# SCHEMAT_WY_WIETLACZA.net
KiCad netlist of a schematic drawn in EAGLE
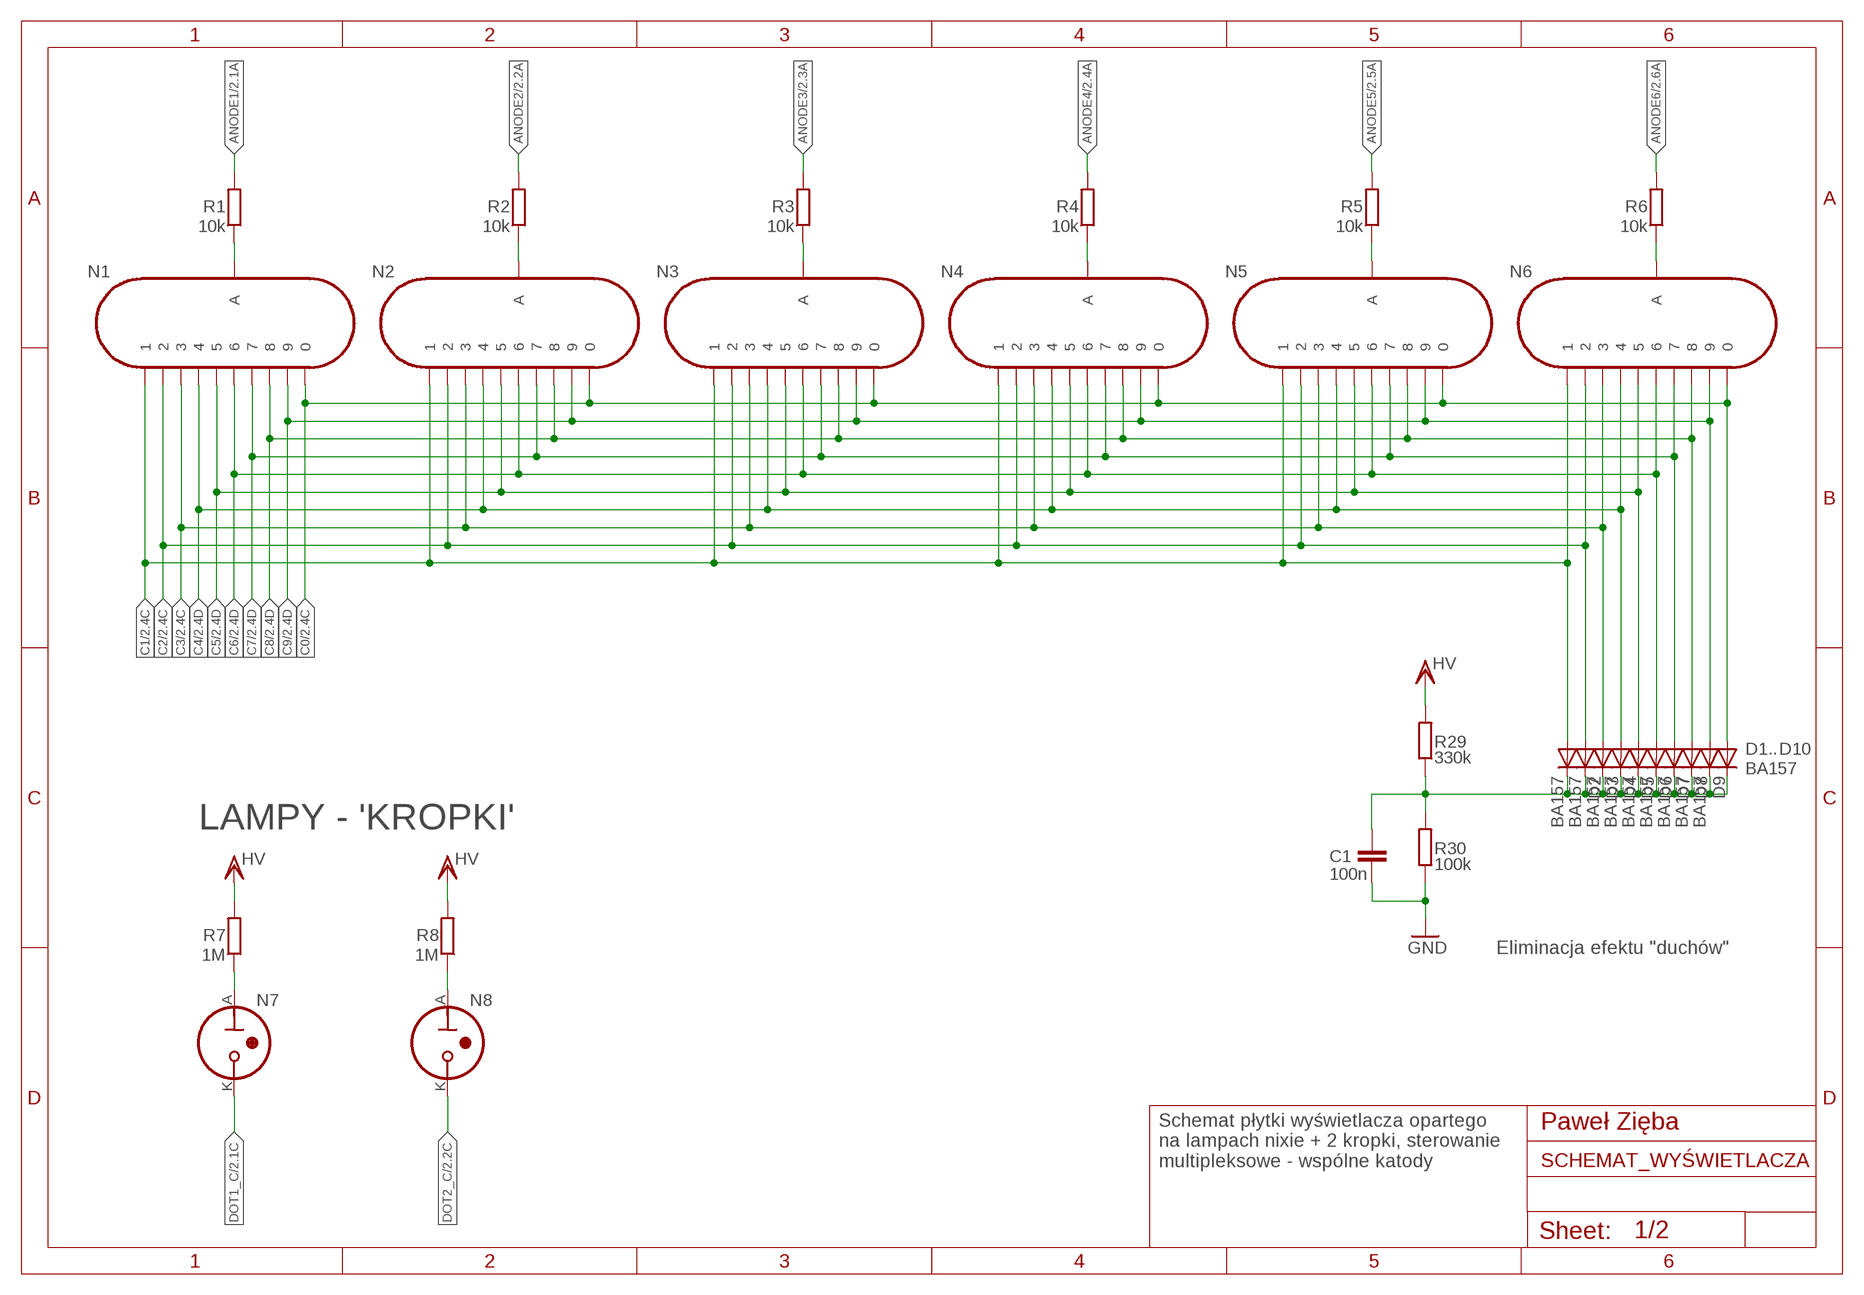
[diagram p0: schematic, sheet 1]
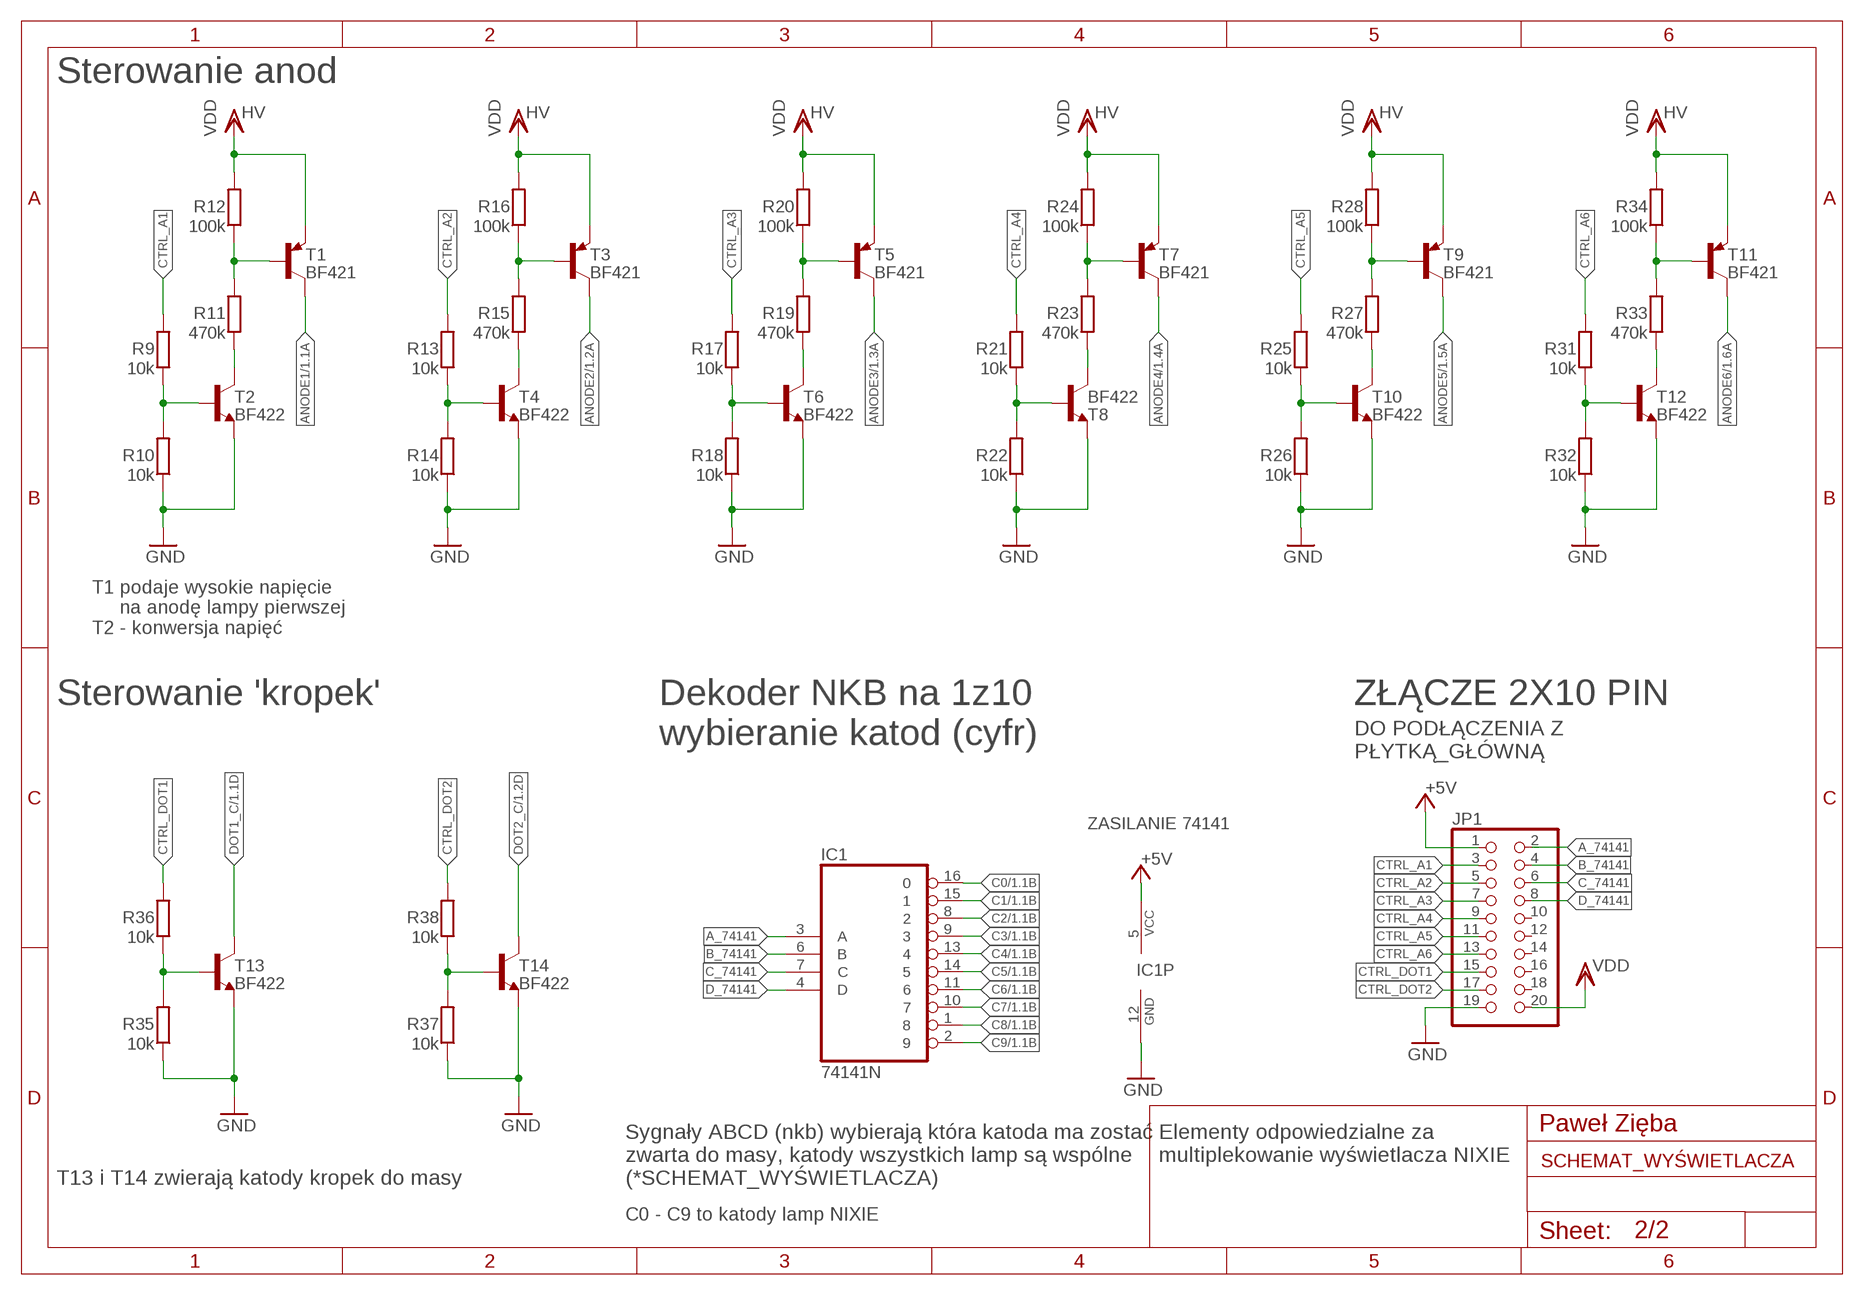
[diagram p1: schematic, sheet 2]

(export (version "E")
  (design (tool "Eeschema 10.0.6"))
  (components
    (comp (ref "IC1")
      (value "74141N")
      (footprint "eagle-import:DIL16")
      (libsource (lib "eagle-import") (part "74141N"))
    )
    (comp (ref "JP1")
      (value "PINHD-2X10")
      (footprint "eagle-import:2X10")
      (libsource (lib "eagle-import") (part "PINHD-2X10"))
    )
    (comp (ref "R9")
      (value "10k")
      (footprint "eagle-import:204_7")
      (libsource (lib "eagle-import") (part "R-EU7"))
    )
    (comp (ref "R10")
      (value "10k")
      (footprint "eagle-import:204_7")
      (libsource (lib "eagle-import") (part "R-EU7"))
    )
    (comp (ref "R11")
      (value "470k")
      (footprint "eagle-import:204_7")
      (libsource (lib "eagle-import") (part "R-EU7"))
    )
    (comp (ref "R12")
      (value "100k")
      (footprint "eagle-import:204_7")
      (libsource (lib "eagle-import") (part "R-EU7"))
    )
    (comp (ref "R13")
      (value "10k")
      (footprint "eagle-import:204_7")
      (libsource (lib "eagle-import") (part "R-EU7"))
    )
    (comp (ref "R14")
      (value "10k")
      (footprint "eagle-import:204_7")
      (libsource (lib "eagle-import") (part "R-EU7"))
    )
    (comp (ref "R15")
      (value "470k")
      (footprint "eagle-import:204_7")
      (libsource (lib "eagle-import") (part "R-EU7"))
    )
    (comp (ref "R16")
      (value "100k")
      (footprint "eagle-import:204_7")
      (libsource (lib "eagle-import") (part "R-EU7"))
    )
    (comp (ref "R17")
      (value "10k")
      (footprint "eagle-import:204_7")
      (libsource (lib "eagle-import") (part "R-EU7"))
    )
    (comp (ref "R18")
      (value "10k")
      (footprint "eagle-import:204_7")
      (libsource (lib "eagle-import") (part "R-EU7"))
    )
    (comp (ref "R19")
      (value "470k")
      (footprint "eagle-import:204_7")
      (libsource (lib "eagle-import") (part "R-EU7"))
    )
    (comp (ref "R20")
      (value "100k")
      (footprint "eagle-import:204_7")
      (libsource (lib "eagle-import") (part "R-EU7"))
    )
    (comp (ref "R21")
      (value "10k")
      (footprint "eagle-import:204_7")
      (libsource (lib "eagle-import") (part "R-EU7"))
    )
    (comp (ref "R22")
      (value "10k")
      (footprint "eagle-import:204_7")
      (libsource (lib "eagle-import") (part "R-EU7"))
    )
    (comp (ref "R23")
      (value "470k")
      (footprint "eagle-import:204_7")
      (libsource (lib "eagle-import") (part "R-EU7"))
    )
    (comp (ref "R24")
      (value "100k")
      (footprint "eagle-import:204_7")
      (libsource (lib "eagle-import") (part "R-EU7"))
    )
    (comp (ref "R25")
      (value "10k")
      (footprint "eagle-import:204_7")
      (libsource (lib "eagle-import") (part "R-EU7"))
    )
    (comp (ref "R26")
      (value "10k")
      (footprint "eagle-import:204_7")
      (libsource (lib "eagle-import") (part "R-EU7"))
    )
    (comp (ref "R27")
      (value "470k")
      (footprint "eagle-import:204_7")
      (libsource (lib "eagle-import") (part "R-EU7"))
    )
    (comp (ref "R28")
      (value "100k")
      (footprint "eagle-import:204_7")
      (libsource (lib "eagle-import") (part "R-EU7"))
    )
    (comp (ref "R31")
      (value "10k")
      (footprint "eagle-import:204_7")
      (libsource (lib "eagle-import") (part "R-EU7"))
    )
    (comp (ref "R32")
      (value "10k")
      (footprint "eagle-import:204_7")
      (libsource (lib "eagle-import") (part "R-EU7"))
    )
    (comp (ref "R33")
      (value "470k")
      (footprint "eagle-import:204_7")
      (libsource (lib "eagle-import") (part "R-EU7"))
    )
    (comp (ref "R34")
      (value "100k")
      (footprint "eagle-import:204_7")
      (libsource (lib "eagle-import") (part "R-EU7"))
    )
    (comp (ref "R35")
      (value "10k")
      (footprint "eagle-import:204_7")
      (libsource (lib "eagle-import") (part "R-EU7"))
    )
    (comp (ref "R36")
      (value "10k")
      (footprint "eagle-import:204_7")
      (libsource (lib "eagle-import") (part "R-EU7"))
    )
    (comp (ref "R37")
      (value "10k")
      (footprint "eagle-import:204_7")
      (libsource (lib "eagle-import") (part "R-EU7"))
    )
    (comp (ref "R38")
      (value "10k")
      (footprint "eagle-import:204_7")
      (libsource (lib "eagle-import") (part "R-EU7"))
    )
    (comp (ref "T1")
      (value "BF421")
      (footprint "eagle-import:TO92-BCE")
      (libsource (lib "eagle-import") (part "BF421"))
    )
    (comp (ref "T2")
      (value "BF422")
      (footprint "eagle-import:TO92-BCE")
      (libsource (lib "eagle-import") (part "-NPN-TO92-BCEBF422"))
    )
    (comp (ref "T3")
      (value "BF421")
      (footprint "eagle-import:TO92-BCE")
      (libsource (lib "eagle-import") (part "BF421"))
    )
    (comp (ref "T4")
      (value "BF422")
      (footprint "eagle-import:TO92-BCE")
      (libsource (lib "eagle-import") (part "-NPN-TO92-BCEBF422"))
    )
    (comp (ref "T5")
      (value "BF421")
      (footprint "eagle-import:TO92-BCE")
      (libsource (lib "eagle-import") (part "BF421"))
    )
    (comp (ref "T6")
      (value "BF422")
      (footprint "eagle-import:TO92-BCE")
      (libsource (lib "eagle-import") (part "-NPN-TO92-BCEBF422"))
    )
    (comp (ref "T7")
      (value "BF421")
      (footprint "eagle-import:TO92-BCE")
      (libsource (lib "eagle-import") (part "BF421"))
    )
    (comp (ref "T8")
      (value "BF422")
      (footprint "eagle-import:TO92-BCE")
      (libsource (lib "eagle-import") (part "-NPN-TO92-BCEBF422"))
    )
    (comp (ref "T9")
      (value "BF421")
      (footprint "eagle-import:TO92-BCE")
      (libsource (lib "eagle-import") (part "BF421"))
    )
    (comp (ref "T10")
      (value "BF422")
      (footprint "eagle-import:TO92-BCE")
      (libsource (lib "eagle-import") (part "-NPN-TO92-BCEBF422"))
    )
    (comp (ref "T11")
      (value "BF421")
      (footprint "eagle-import:TO92-BCE")
      (libsource (lib "eagle-import") (part "BF421"))
    )
    (comp (ref "T12")
      (value "BF422")
      (footprint "eagle-import:TO92-BCE")
      (libsource (lib "eagle-import") (part "-NPN-TO92-BCEBF422"))
    )
    (comp (ref "T13")
      (value "BF422")
      (footprint "eagle-import:TO92-BCE")
      (libsource (lib "eagle-import") (part "-NPN-TO92-BCEBF422"))
    )
    (comp (ref "T14")
      (value "BF422")
      (footprint "eagle-import:TO92-BCE")
      (libsource (lib "eagle-import") (part "-NPN-TO92-BCEBF422"))
    )
    (comp (ref "C1")
      (value "100n")
      (footprint "eagle-import:C50-45-75")
      (libsource (lib "eagle-import") (part "C-EU050-045-075"))
    )
    (comp (ref "D1")
      (value "BA157")
      (footprint "eagle-import:P1-10")
      (libsource (lib "eagle-import") (part "BA157"))
    )
    (comp (ref "D2")
      (value "BA157")
      (footprint "eagle-import:P1-10")
      (libsource (lib "eagle-import") (part "BA157"))
    )
    (comp (ref "D3")
      (value "BA157")
      (footprint "eagle-import:P1-10")
      (libsource (lib "eagle-import") (part "BA157"))
    )
    (comp (ref "D4")
      (value "BA157")
      (footprint "eagle-import:P1-10")
      (libsource (lib "eagle-import") (part "BA157"))
    )
    (comp (ref "D5")
      (value "BA157")
      (footprint "eagle-import:P1-10")
      (libsource (lib "eagle-import") (part "BA157"))
    )
    (comp (ref "D6")
      (value "BA157")
      (footprint "eagle-import:P1-10")
      (libsource (lib "eagle-import") (part "BA157"))
    )
    (comp (ref "D7")
      (value "BA157")
      (footprint "eagle-import:P1-10")
      (libsource (lib "eagle-import") (part "BA157"))
    )
    (comp (ref "D8")
      (value "BA157")
      (footprint "eagle-import:P1-10")
      (libsource (lib "eagle-import") (part "BA157"))
    )
    (comp (ref "D9")
      (value "BA157")
      (footprint "eagle-import:P1-10")
      (libsource (lib "eagle-import") (part "BA157"))
    )
    (comp (ref "D10")
      (value "BA157")
      (footprint "eagle-import:P1-10")
      (libsource (lib "eagle-import") (part "BA157"))
    )
    (comp (ref "N1")
      (value "IN-8")
      (footprint "eagle-import:IN-8")
      (libsource (lib "eagle-import") (part "IN-8"))
    )
    (comp (ref "N2")
      (value "IN-8")
      (footprint "eagle-import:IN-8")
      (libsource (lib "eagle-import") (part "IN-8"))
    )
    (comp (ref "N3")
      (value "IN-8")
      (footprint "eagle-import:IN-8")
      (libsource (lib "eagle-import") (part "IN-8"))
    )
    (comp (ref "N4")
      (value "IN-8")
      (footprint "eagle-import:IN-8")
      (libsource (lib "eagle-import") (part "IN-8"))
    )
    (comp (ref "N5")
      (value "IN-8")
      (footprint "eagle-import:IN-8")
      (libsource (lib "eagle-import") (part "IN-8"))
    )
    (comp (ref "N6")
      (value "IN-8")
      (footprint "eagle-import:IN-8")
      (libsource (lib "eagle-import") (part "IN-8"))
    )
    (comp (ref "N7")
      (value "IN-3")
      (footprint "eagle-import:IN-3")
      (libsource (lib "eagle-import") (part "IN-3"))
    )
    (comp (ref "N8")
      (value "IN-3")
      (footprint "eagle-import:IN-3")
      (libsource (lib "eagle-import") (part "IN-3"))
    )
    (comp (ref "R1")
      (value "10k")
      (footprint "eagle-import:204_7")
      (libsource (lib "eagle-import") (part "R-EU7"))
    )
    (comp (ref "R2")
      (value "10k")
      (footprint "eagle-import:204_7")
      (libsource (lib "eagle-import") (part "R-EU7"))
    )
    (comp (ref "R3")
      (value "10k")
      (footprint "eagle-import:204_7")
      (libsource (lib "eagle-import") (part "R-EU7"))
    )
    (comp (ref "R4")
      (value "10k")
      (footprint "eagle-import:204_7")
      (libsource (lib "eagle-import") (part "R-EU7"))
    )
    (comp (ref "R5")
      (value "10k")
      (footprint "eagle-import:204_7")
      (libsource (lib "eagle-import") (part "R-EU7"))
    )
    (comp (ref "R6")
      (value "10k")
      (footprint "eagle-import:204_7")
      (libsource (lib "eagle-import") (part "R-EU7"))
    )
    (comp (ref "R7")
      (value "1M")
      (footprint "eagle-import:204_7")
      (libsource (lib "eagle-import") (part "R-EU7"))
    )
    (comp (ref "R8")
      (value "1M")
      (footprint "eagle-import:204_7")
      (libsource (lib "eagle-import") (part "R-EU7"))
    )
    (comp (ref "R29")
      (value "330k")
      (footprint "eagle-import:204_7")
      (libsource (lib "eagle-import") (part "R-EU7"))
    )
    (comp (ref "R30")
      (value "100k")
      (footprint "eagle-import:204_7")
      (libsource (lib "eagle-import") (part "R-EU7"))
    )
  )
  (nets
    (net (code "1") (name "+5V") (class "Default")
      (node (ref "IC1") (pin "5") (pinfunction "VCC_5") (pintype "power_in"))
      (node (ref "JP1") (pin "1") (pinfunction "1_1") (pintype "passive"))
    )
    (net (code "2") (name "ANODE1") (class "Default")
      (node (ref "R1") (pin "P$2") (pinfunction "2_P$2") (pintype "passive"))
      (node (ref "T1") (pin "C") (pinfunction "C_C") (pintype "passive"))
    )
    (net (code "3") (name "ANODE2") (class "Default")
      (node (ref "R2") (pin "P$2") (pinfunction "2_P$2") (pintype "passive"))
      (node (ref "T3") (pin "C") (pinfunction "C_C") (pintype "passive"))
    )
    (net (code "4") (name "ANODE3") (class "Default")
      (node (ref "R3") (pin "P$2") (pinfunction "2_P$2") (pintype "passive"))
      (node (ref "T5") (pin "C") (pinfunction "C_C") (pintype "passive"))
    )
    (net (code "5") (name "ANODE4") (class "Default")
      (node (ref "R4") (pin "P$2") (pinfunction "2_P$2") (pintype "passive"))
      (node (ref "T7") (pin "C") (pinfunction "C_C") (pintype "passive"))
    )
    (net (code "6") (name "ANODE5") (class "Default")
      (node (ref "R5") (pin "P$2") (pinfunction "2_P$2") (pintype "passive"))
      (node (ref "T9") (pin "C") (pinfunction "C_C") (pintype "passive"))
    )
    (net (code "7") (name "ANODE6") (class "Default")
      (node (ref "R6") (pin "P$2") (pinfunction "2_P$2") (pintype "passive"))
      (node (ref "T11") (pin "C") (pinfunction "C_C") (pintype "passive"))
    )
    (net (code "8") (name "A_74141") (class "Default")
      (node (ref "IC1") (pin "3") (pinfunction "A_3") (pintype "input"))
      (node (ref "JP1") (pin "2") (pinfunction "2_2") (pintype "passive"))
    )
    (net (code "9") (name "B_74141") (class "Default")
      (node (ref "IC1") (pin "6") (pinfunction "B_6") (pintype "input"))
      (node (ref "JP1") (pin "4") (pinfunction "4_4") (pintype "passive"))
    )
    (net (code "10") (name "C0") (class "Default")
      (node (ref "D10") (pin "A") (pinfunction "A_A") (pintype "passive"))
      (node (ref "IC1") (pin "16") (pinfunction "0_16") (pintype "open_collector"))
      (node (ref "N1") (pin "0") (pinfunction "0_0") (pintype "bidirectional"))
      (node (ref "N2") (pin "0") (pinfunction "0_0") (pintype "bidirectional"))
      (node (ref "N3") (pin "0") (pinfunction "0_0") (pintype "bidirectional"))
      (node (ref "N4") (pin "0") (pinfunction "0_0") (pintype "bidirectional"))
      (node (ref "N5") (pin "0") (pinfunction "0_0") (pintype "bidirectional"))
      (node (ref "N6") (pin "0") (pinfunction "0_0") (pintype "bidirectional"))
    )
    (net (code "11") (name "C1") (class "Default")
      (node (ref "D1") (pin "A") (pinfunction "A_A") (pintype "passive"))
      (node (ref "IC1") (pin "15") (pinfunction "1_15") (pintype "open_collector"))
      (node (ref "N1") (pin "1") (pinfunction "1_1") (pintype "bidirectional"))
      (node (ref "N2") (pin "1") (pinfunction "1_1") (pintype "bidirectional"))
      (node (ref "N3") (pin "1") (pinfunction "1_1") (pintype "bidirectional"))
      (node (ref "N4") (pin "1") (pinfunction "1_1") (pintype "bidirectional"))
      (node (ref "N5") (pin "1") (pinfunction "1_1") (pintype "bidirectional"))
      (node (ref "N6") (pin "1") (pinfunction "1_1") (pintype "bidirectional"))
    )
    (net (code "12") (name "C2") (class "Default")
      (node (ref "D2") (pin "A") (pinfunction "A_A") (pintype "passive"))
      (node (ref "IC1") (pin "8") (pinfunction "2_8") (pintype "open_collector"))
      (node (ref "N1") (pin "2") (pinfunction "2_2") (pintype "bidirectional"))
      (node (ref "N2") (pin "2") (pinfunction "2_2") (pintype "bidirectional"))
      (node (ref "N3") (pin "2") (pinfunction "2_2") (pintype "bidirectional"))
      (node (ref "N4") (pin "2") (pinfunction "2_2") (pintype "bidirectional"))
      (node (ref "N5") (pin "2") (pinfunction "2_2") (pintype "bidirectional"))
      (node (ref "N6") (pin "2") (pinfunction "2_2") (pintype "bidirectional"))
    )
    (net (code "13") (name "C3") (class "Default")
      (node (ref "D3") (pin "A") (pinfunction "A_A") (pintype "passive"))
      (node (ref "IC1") (pin "9") (pinfunction "3_9") (pintype "open_collector"))
      (node (ref "N1") (pin "3") (pinfunction "3_3") (pintype "bidirectional"))
      (node (ref "N2") (pin "3") (pinfunction "3_3") (pintype "bidirectional"))
      (node (ref "N3") (pin "3") (pinfunction "3_3") (pintype "bidirectional"))
      (node (ref "N4") (pin "3") (pinfunction "3_3") (pintype "bidirectional"))
      (node (ref "N5") (pin "3") (pinfunction "3_3") (pintype "bidirectional"))
      (node (ref "N6") (pin "3") (pinfunction "3_3") (pintype "bidirectional"))
    )
    (net (code "14") (name "C4") (class "Default")
      (node (ref "D4") (pin "A") (pinfunction "A_A") (pintype "passive"))
      (node (ref "IC1") (pin "13") (pinfunction "4_13") (pintype "open_collector"))
      (node (ref "N1") (pin "4") (pinfunction "4_4") (pintype "bidirectional"))
      (node (ref "N2") (pin "4") (pinfunction "4_4") (pintype "bidirectional"))
      (node (ref "N3") (pin "4") (pinfunction "4_4") (pintype "bidirectional"))
      (node (ref "N4") (pin "4") (pinfunction "4_4") (pintype "bidirectional"))
      (node (ref "N5") (pin "4") (pinfunction "4_4") (pintype "bidirectional"))
      (node (ref "N6") (pin "4") (pinfunction "4_4") (pintype "bidirectional"))
    )
    (net (code "15") (name "C5") (class "Default")
      (node (ref "D5") (pin "A") (pinfunction "A_A") (pintype "passive"))
      (node (ref "IC1") (pin "14") (pinfunction "5_14") (pintype "open_collector"))
      (node (ref "N1") (pin "5") (pinfunction "5_5") (pintype "bidirectional"))
      (node (ref "N2") (pin "5") (pinfunction "5_5") (pintype "bidirectional"))
      (node (ref "N3") (pin "5") (pinfunction "5_5") (pintype "bidirectional"))
      (node (ref "N4") (pin "5") (pinfunction "5_5") (pintype "bidirectional"))
      (node (ref "N5") (pin "5") (pinfunction "5_5") (pintype "bidirectional"))
      (node (ref "N6") (pin "5") (pinfunction "5_5") (pintype "bidirectional"))
    )
    (net (code "16") (name "C6") (class "Default")
      (node (ref "D6") (pin "A") (pinfunction "A_A") (pintype "passive"))
      (node (ref "IC1") (pin "11") (pinfunction "6_11") (pintype "open_collector"))
      (node (ref "N1") (pin "6") (pinfunction "6_6") (pintype "bidirectional"))
      (node (ref "N2") (pin "6") (pinfunction "6_6") (pintype "bidirectional"))
      (node (ref "N3") (pin "6") (pinfunction "6_6") (pintype "bidirectional"))
      (node (ref "N4") (pin "6") (pinfunction "6_6") (pintype "bidirectional"))
      (node (ref "N5") (pin "6") (pinfunction "6_6") (pintype "bidirectional"))
      (node (ref "N6") (pin "6") (pinfunction "6_6") (pintype "bidirectional"))
    )
    (net (code "17") (name "C7") (class "Default")
      (node (ref "D7") (pin "A") (pinfunction "A_A") (pintype "passive"))
      (node (ref "IC1") (pin "10") (pinfunction "7_10") (pintype "open_collector"))
      (node (ref "N1") (pin "7") (pinfunction "7_7") (pintype "bidirectional"))
      (node (ref "N2") (pin "7") (pinfunction "7_7") (pintype "bidirectional"))
      (node (ref "N3") (pin "7") (pinfunction "7_7") (pintype "bidirectional"))
      (node (ref "N4") (pin "7") (pinfunction "7_7") (pintype "bidirectional"))
      (node (ref "N5") (pin "7") (pinfunction "7_7") (pintype "bidirectional"))
      (node (ref "N6") (pin "7") (pinfunction "7_7") (pintype "bidirectional"))
    )
    (net (code "18") (name "C8") (class "Default")
      (node (ref "D8") (pin "A") (pinfunction "A_A") (pintype "passive"))
      (node (ref "IC1") (pin "1") (pinfunction "8_1") (pintype "open_collector"))
      (node (ref "N1") (pin "8") (pinfunction "8_8") (pintype "bidirectional"))
      (node (ref "N2") (pin "8") (pinfunction "8_8") (pintype "bidirectional"))
      (node (ref "N3") (pin "8") (pinfunction "8_8") (pintype "bidirectional"))
      (node (ref "N4") (pin "8") (pinfunction "8_8") (pintype "bidirectional"))
      (node (ref "N5") (pin "8") (pinfunction "8_8") (pintype "bidirectional"))
      (node (ref "N6") (pin "8") (pinfunction "8_8") (pintype "bidirectional"))
    )
    (net (code "19") (name "C9") (class "Default")
      (node (ref "D9") (pin "A") (pinfunction "A_A") (pintype "passive"))
      (node (ref "IC1") (pin "2") (pinfunction "9_2") (pintype "open_collector"))
      (node (ref "N1") (pin "9") (pinfunction "9_9") (pintype "bidirectional"))
      (node (ref "N2") (pin "9") (pinfunction "9_9") (pintype "bidirectional"))
      (node (ref "N3") (pin "9") (pinfunction "9_9") (pintype "bidirectional"))
      (node (ref "N4") (pin "9") (pinfunction "9_9") (pintype "bidirectional"))
      (node (ref "N5") (pin "9") (pinfunction "9_9") (pintype "bidirectional"))
      (node (ref "N6") (pin "9") (pinfunction "9_9") (pintype "bidirectional"))
    )
    (net (code "20") (name "CTRL_A1") (class "Default")
      (node (ref "JP1") (pin "3") (pinfunction "3_3") (pintype "passive"))
      (node (ref "R9") (pin "P$2") (pinfunction "2_P$2") (pintype "passive"))
    )
    (net (code "21") (name "CTRL_A2") (class "Default")
      (node (ref "JP1") (pin "5") (pinfunction "5_5") (pintype "passive"))
      (node (ref "R13") (pin "P$2") (pinfunction "2_P$2") (pintype "passive"))
    )
    (net (code "22") (name "CTRL_A3") (class "Default")
      (node (ref "JP1") (pin "7") (pinfunction "7_7") (pintype "passive"))
      (node (ref "R17") (pin "P$2") (pinfunction "2_P$2") (pintype "passive"))
    )
    (net (code "23") (name "CTRL_A4") (class "Default")
      (node (ref "JP1") (pin "9") (pinfunction "9_9") (pintype "passive"))
      (node (ref "R21") (pin "P$2") (pinfunction "2_P$2") (pintype "passive"))
    )
    (net (code "24") (name "CTRL_A5") (class "Default")
      (node (ref "JP1") (pin "11") (pinfunction "11_11") (pintype "passive"))
      (node (ref "R25") (pin "P$2") (pinfunction "2_P$2") (pintype "passive"))
    )
    (net (code "25") (name "CTRL_A6") (class "Default")
      (node (ref "JP1") (pin "13") (pinfunction "13_13") (pintype "passive"))
      (node (ref "R31") (pin "P$2") (pinfunction "2_P$2") (pintype "passive"))
    )
    (net (code "26") (name "CTRL_DOT1") (class "Default")
      (node (ref "JP1") (pin "15") (pinfunction "15_15") (pintype "passive"))
      (node (ref "R36") (pin "P$2") (pinfunction "2_P$2") (pintype "passive"))
    )
    (net (code "27") (name "CTRL_DOT2") (class "Default")
      (node (ref "JP1") (pin "17") (pinfunction "17_17") (pintype "passive"))
      (node (ref "R38") (pin "P$2") (pinfunction "2_P$2") (pintype "passive"))
    )
    (net (code "28") (name "C_74141") (class "Default")
      (node (ref "IC1") (pin "7") (pinfunction "C_7") (pintype "input"))
      (node (ref "JP1") (pin "6") (pinfunction "6_6") (pintype "passive"))
    )
    (net (code "29") (name "DOT1_C") (class "Default")
      (node (ref "N7") (pin "K") (pinfunction "K_K") (pintype "bidirectional"))
      (node (ref "T13") (pin "C") (pinfunction "C_C") (pintype "passive"))
    )
    (net (code "30") (name "DOT2_C") (class "Default")
      (node (ref "N8") (pin "K") (pinfunction "K_K") (pintype "bidirectional"))
      (node (ref "T14") (pin "C") (pinfunction "C_C") (pintype "passive"))
    )
    (net (code "31") (name "D_74141") (class "Default")
      (node (ref "IC1") (pin "4") (pinfunction "D_4") (pintype "input"))
      (node (ref "JP1") (pin "8") (pinfunction "8_8") (pintype "passive"))
    )
    (net (code "32") (name "GND") (class "Default")
      (node (ref "C1") (pin "P$2") (pinfunction "2_P$2") (pintype "passive"))
      (node (ref "IC1") (pin "12") (pinfunction "GND_12") (pintype "power_in"))
      (node (ref "JP1") (pin "19") (pinfunction "19_19") (pintype "passive"))
      (node (ref "R10") (pin "P$1") (pinfunction "1_P$1") (pintype "passive"))
      (node (ref "R14") (pin "P$1") (pinfunction "1_P$1") (pintype "passive"))
      (node (ref "R18") (pin "P$1") (pinfunction "1_P$1") (pintype "passive"))
      (node (ref "R22") (pin "P$1") (pinfunction "1_P$1") (pintype "passive"))
      (node (ref "R26") (pin "P$1") (pinfunction "1_P$1") (pintype "passive"))
      (node (ref "R30") (pin "P$1") (pinfunction "1_P$1") (pintype "passive"))
      (node (ref "R32") (pin "P$1") (pinfunction "1_P$1") (pintype "passive"))
      (node (ref "R35") (pin "P$1") (pinfunction "1_P$1") (pintype "passive"))
      (node (ref "R37") (pin "P$1") (pinfunction "1_P$1") (pintype "passive"))
      (node (ref "T10") (pin "E") (pinfunction "E_E") (pintype "passive"))
      (node (ref "T12") (pin "E") (pinfunction "E_E") (pintype "passive"))
      (node (ref "T13") (pin "E") (pinfunction "E_E") (pintype "passive"))
      (node (ref "T14") (pin "E") (pinfunction "E_E") (pintype "passive"))
      (node (ref "T2") (pin "E") (pinfunction "E_E") (pintype "passive"))
      (node (ref "T4") (pin "E") (pinfunction "E_E") (pintype "passive"))
      (node (ref "T6") (pin "E") (pinfunction "E_E") (pintype "passive"))
      (node (ref "T8") (pin "E") (pinfunction "E_E") (pintype "passive"))
    )
    (net (code "33") (name "HV") (class "Default")
      (node (ref "JP1") (pin "20") (pinfunction "20_20") (pintype "passive"))
      (node (ref "R12") (pin "P$2") (pinfunction "2_P$2") (pintype "passive"))
      (node (ref "R16") (pin "P$2") (pinfunction "2_P$2") (pintype "passive"))
      (node (ref "R20") (pin "P$2") (pinfunction "2_P$2") (pintype "passive"))
      (node (ref "R24") (pin "P$2") (pinfunction "2_P$2") (pintype "passive"))
      (node (ref "R28") (pin "P$2") (pinfunction "2_P$2") (pintype "passive"))
      (node (ref "R29") (pin "P$2") (pinfunction "2_P$2") (pintype "passive"))
      (node (ref "R34") (pin "P$2") (pinfunction "2_P$2") (pintype "passive"))
      (node (ref "R7") (pin "P$2") (pinfunction "2_P$2") (pintype "passive"))
      (node (ref "R8") (pin "P$2") (pinfunction "2_P$2") (pintype "passive"))
      (node (ref "T1") (pin "E") (pinfunction "E_E") (pintype "passive"))
      (node (ref "T11") (pin "E") (pinfunction "E_E") (pintype "passive"))
      (node (ref "T3") (pin "E") (pinfunction "E_E") (pintype "passive"))
      (node (ref "T5") (pin "E") (pinfunction "E_E") (pintype "passive"))
      (node (ref "T7") (pin "E") (pinfunction "E_E") (pintype "passive"))
      (node (ref "T9") (pin "E") (pinfunction "E_E") (pintype "passive"))
    )
    (net (code "34") (name "Net-(C1-1)") (class "Default")
      (node (ref "C1") (pin "P$1") (pinfunction "1_P$1") (pintype "passive"))
      (node (ref "D1") (pin "C") (pinfunction "C_C") (pintype "passive"))
      (node (ref "D10") (pin "C") (pinfunction "C_C") (pintype "passive"))
      (node (ref "D2") (pin "C") (pinfunction "C_C") (pintype "passive"))
      (node (ref "D3") (pin "C") (pinfunction "C_C") (pintype "passive"))
      (node (ref "D4") (pin "C") (pinfunction "C_C") (pintype "passive"))
      (node (ref "D5") (pin "C") (pinfunction "C_C") (pintype "passive"))
      (node (ref "D6") (pin "C") (pinfunction "C_C") (pintype "passive"))
      (node (ref "D7") (pin "C") (pinfunction "C_C") (pintype "passive"))
      (node (ref "D8") (pin "C") (pinfunction "C_C") (pintype "passive"))
      (node (ref "D9") (pin "C") (pinfunction "C_C") (pintype "passive"))
      (node (ref "R29") (pin "P$1") (pinfunction "1_P$1") (pintype "passive"))
      (node (ref "R30") (pin "P$2") (pinfunction "2_P$2") (pintype "passive"))
    )
    (net (code "35") (name "Net-(R1-1)") (class "Default")
      (node (ref "N1") (pin "A") (pinfunction "A_A") (pintype "bidirectional"))
      (node (ref "R1") (pin "P$1") (pinfunction "1_P$1") (pintype "passive"))
    )
    (net (code "36") (name "Net-(R2-1)") (class "Default")
      (node (ref "N2") (pin "A") (pinfunction "A_A") (pintype "bidirectional"))
      (node (ref "R2") (pin "P$1") (pinfunction "1_P$1") (pintype "passive"))
    )
    (net (code "37") (name "Net-(R3-1)") (class "Default")
      (node (ref "N3") (pin "A") (pinfunction "A_A") (pintype "bidirectional"))
      (node (ref "R3") (pin "P$1") (pinfunction "1_P$1") (pintype "passive"))
    )
    (net (code "38") (name "Net-(R4-1)") (class "Default")
      (node (ref "N4") (pin "A") (pinfunction "A_A") (pintype "bidirectional"))
      (node (ref "R4") (pin "P$1") (pinfunction "1_P$1") (pintype "passive"))
    )
    (net (code "39") (name "Net-(R5-1)") (class "Default")
      (node (ref "N5") (pin "A") (pinfunction "A_A") (pintype "bidirectional"))
      (node (ref "R5") (pin "P$1") (pinfunction "1_P$1") (pintype "passive"))
    )
    (net (code "40") (name "Net-(R6-1)") (class "Default")
      (node (ref "N6") (pin "A") (pinfunction "A_A") (pintype "bidirectional"))
      (node (ref "R6") (pin "P$1") (pinfunction "1_P$1") (pintype "passive"))
    )
    (net (code "41") (name "Net-(R7-1)") (class "Default")
      (node (ref "N7") (pin "A") (pinfunction "A_A") (pintype "bidirectional"))
      (node (ref "R7") (pin "P$1") (pinfunction "1_P$1") (pintype "passive"))
    )
    (net (code "42") (name "Net-(R8-1)") (class "Default")
      (node (ref "N8") (pin "A") (pinfunction "A_A") (pintype "bidirectional"))
      (node (ref "R8") (pin "P$1") (pinfunction "1_P$1") (pintype "passive"))
    )
    (net (code "43") (name "Net-(R10-2)") (class "Default")
      (node (ref "R10") (pin "P$2") (pinfunction "2_P$2") (pintype "passive"))
      (node (ref "R9") (pin "P$1") (pinfunction "1_P$1") (pintype "passive"))
      (node (ref "T2") (pin "B") (pinfunction "B_B") (pintype "passive"))
    )
    (net (code "44") (name "Net-(R11-1)") (class "Default")
      (node (ref "R11") (pin "P$1") (pinfunction "1_P$1") (pintype "passive"))
      (node (ref "T2") (pin "C") (pinfunction "C_C") (pintype "passive"))
    )
    (net (code "45") (name "Net-(R11-2)") (class "Default")
      (node (ref "R11") (pin "P$2") (pinfunction "2_P$2") (pintype "passive"))
      (node (ref "R12") (pin "P$1") (pinfunction "1_P$1") (pintype "passive"))
      (node (ref "T1") (pin "B") (pinfunction "B_B") (pintype "passive"))
    )
    (net (code "46") (name "Net-(R13-1)") (class "Default")
      (node (ref "R13") (pin "P$1") (pinfunction "1_P$1") (pintype "passive"))
      (node (ref "R14") (pin "P$2") (pinfunction "2_P$2") (pintype "passive"))
      (node (ref "T4") (pin "B") (pinfunction "B_B") (pintype "passive"))
    )
    (net (code "47") (name "Net-(R15-1)") (class "Default")
      (node (ref "R15") (pin "P$1") (pinfunction "1_P$1") (pintype "passive"))
      (node (ref "T4") (pin "C") (pinfunction "C_C") (pintype "passive"))
    )
    (net (code "48") (name "Net-(R15-2)") (class "Default")
      (node (ref "R15") (pin "P$2") (pinfunction "2_P$2") (pintype "passive"))
      (node (ref "R16") (pin "P$1") (pinfunction "1_P$1") (pintype "passive"))
      (node (ref "T3") (pin "B") (pinfunction "B_B") (pintype "passive"))
    )
    (net (code "49") (name "Net-(R17-1)") (class "Default")
      (node (ref "R17") (pin "P$1") (pinfunction "1_P$1") (pintype "passive"))
      (node (ref "R18") (pin "P$2") (pinfunction "2_P$2") (pintype "passive"))
      (node (ref "T6") (pin "B") (pinfunction "B_B") (pintype "passive"))
    )
    (net (code "50") (name "Net-(R19-1)") (class "Default")
      (node (ref "R19") (pin "P$1") (pinfunction "1_P$1") (pintype "passive"))
      (node (ref "T6") (pin "C") (pinfunction "C_C") (pintype "passive"))
    )
    (net (code "51") (name "Net-(R19-2)") (class "Default")
      (node (ref "R19") (pin "P$2") (pinfunction "2_P$2") (pintype "passive"))
      (node (ref "R20") (pin "P$1") (pinfunction "1_P$1") (pintype "passive"))
      (node (ref "T5") (pin "B") (pinfunction "B_B") (pintype "passive"))
    )
    (net (code "52") (name "Net-(R21-1)") (class "Default")
      (node (ref "R21") (pin "P$1") (pinfunction "1_P$1") (pintype "passive"))
      (node (ref "R22") (pin "P$2") (pinfunction "2_P$2") (pintype "passive"))
      (node (ref "T8") (pin "B") (pinfunction "B_B") (pintype "passive"))
    )
    (net (code "53") (name "Net-(R23-1)") (class "Default")
      (node (ref "R23") (pin "P$1") (pinfunction "1_P$1") (pintype "passive"))
      (node (ref "T8") (pin "C") (pinfunction "C_C") (pintype "passive"))
    )
    (net (code "54") (name "Net-(R23-2)") (class "Default")
      (node (ref "R23") (pin "P$2") (pinfunction "2_P$2") (pintype "passive"))
      (node (ref "R24") (pin "P$1") (pinfunction "1_P$1") (pintype "passive"))
      (node (ref "T7") (pin "B") (pinfunction "B_B") (pintype "passive"))
    )
    (net (code "55") (name "Net-(R25-1)") (class "Default")
      (node (ref "R25") (pin "P$1") (pinfunction "1_P$1") (pintype "passive"))
      (node (ref "R26") (pin "P$2") (pinfunction "2_P$2") (pintype "passive"))
      (node (ref "T10") (pin "B") (pinfunction "B_B") (pintype "passive"))
    )
    (net (code "56") (name "Net-(R27-1)") (class "Default")
      (node (ref "R27") (pin "P$1") (pinfunction "1_P$1") (pintype "passive"))
      (node (ref "T10") (pin "C") (pinfunction "C_C") (pintype "passive"))
    )
    (net (code "57") (name "Net-(R27-2)") (class "Default")
      (node (ref "R27") (pin "P$2") (pinfunction "2_P$2") (pintype "passive"))
      (node (ref "R28") (pin "P$1") (pinfunction "1_P$1") (pintype "passive"))
      (node (ref "T9") (pin "B") (pinfunction "B_B") (pintype "passive"))
    )
    (net (code "58") (name "Net-(R31-1)") (class "Default")
      (node (ref "R31") (pin "P$1") (pinfunction "1_P$1") (pintype "passive"))
      (node (ref "R32") (pin "P$2") (pinfunction "2_P$2") (pintype "passive"))
      (node (ref "T12") (pin "B") (pinfunction "B_B") (pintype "passive"))
    )
    (net (code "59") (name "Net-(R33-1)") (class "Default")
      (node (ref "R33") (pin "P$1") (pinfunction "1_P$1") (pintype "passive"))
      (node (ref "T12") (pin "C") (pinfunction "C_C") (pintype "passive"))
    )
    (net (code "60") (name "Net-(R33-2)") (class "Default")
      (node (ref "R33") (pin "P$2") (pinfunction "2_P$2") (pintype "passive"))
      (node (ref "R34") (pin "P$1") (pinfunction "1_P$1") (pintype "passive"))
      (node (ref "T11") (pin "B") (pinfunction "B_B") (pintype "passive"))
    )
    (net (code "61") (name "Net-(R35-2)") (class "Default")
      (node (ref "R35") (pin "P$2") (pinfunction "2_P$2") (pintype "passive"))
      (node (ref "R36") (pin "P$1") (pinfunction "1_P$1") (pintype "passive"))
      (node (ref "T13") (pin "B") (pinfunction "B_B") (pintype "passive"))
    )
    (net (code "62") (name "Net-(R37-2)") (class "Default")
      (node (ref "R37") (pin "P$2") (pinfunction "2_P$2") (pintype "passive"))
      (node (ref "R38") (pin "P$1") (pinfunction "1_P$1") (pintype "passive"))
      (node (ref "T14") (pin "B") (pinfunction "B_B") (pintype "passive"))
    )
    (net (code "63") (name "unconnected-(JP1-Pad10)") (class "Default")
      (node (ref "JP1") (pin "10") (pinfunction "10_10") (pintype "passive"))
    )
    (net (code "64") (name "unconnected-(JP1-Pad12)") (class "Default")
      (node (ref "JP1") (pin "12") (pinfunction "12_12") (pintype "passive"))
    )
    (net (code "65") (name "unconnected-(JP1-Pad14)") (class "Default")
      (node (ref "JP1") (pin "14") (pinfunction "14_14") (pintype "passive"))
    )
    (net (code "66") (name "unconnected-(JP1-Pad16)") (class "Default")
      (node (ref "JP1") (pin "16") (pinfunction "16_16") (pintype "passive"))
    )
    (net (code "67") (name "unconnected-(JP1-Pad18)") (class "Default")
      (node (ref "JP1") (pin "18") (pinfunction "18_18") (pintype "passive"))
    )
  )
)
